# SOCPowerDecoupling.net
KiCad netlist of a schematic drawn in Altium Designer
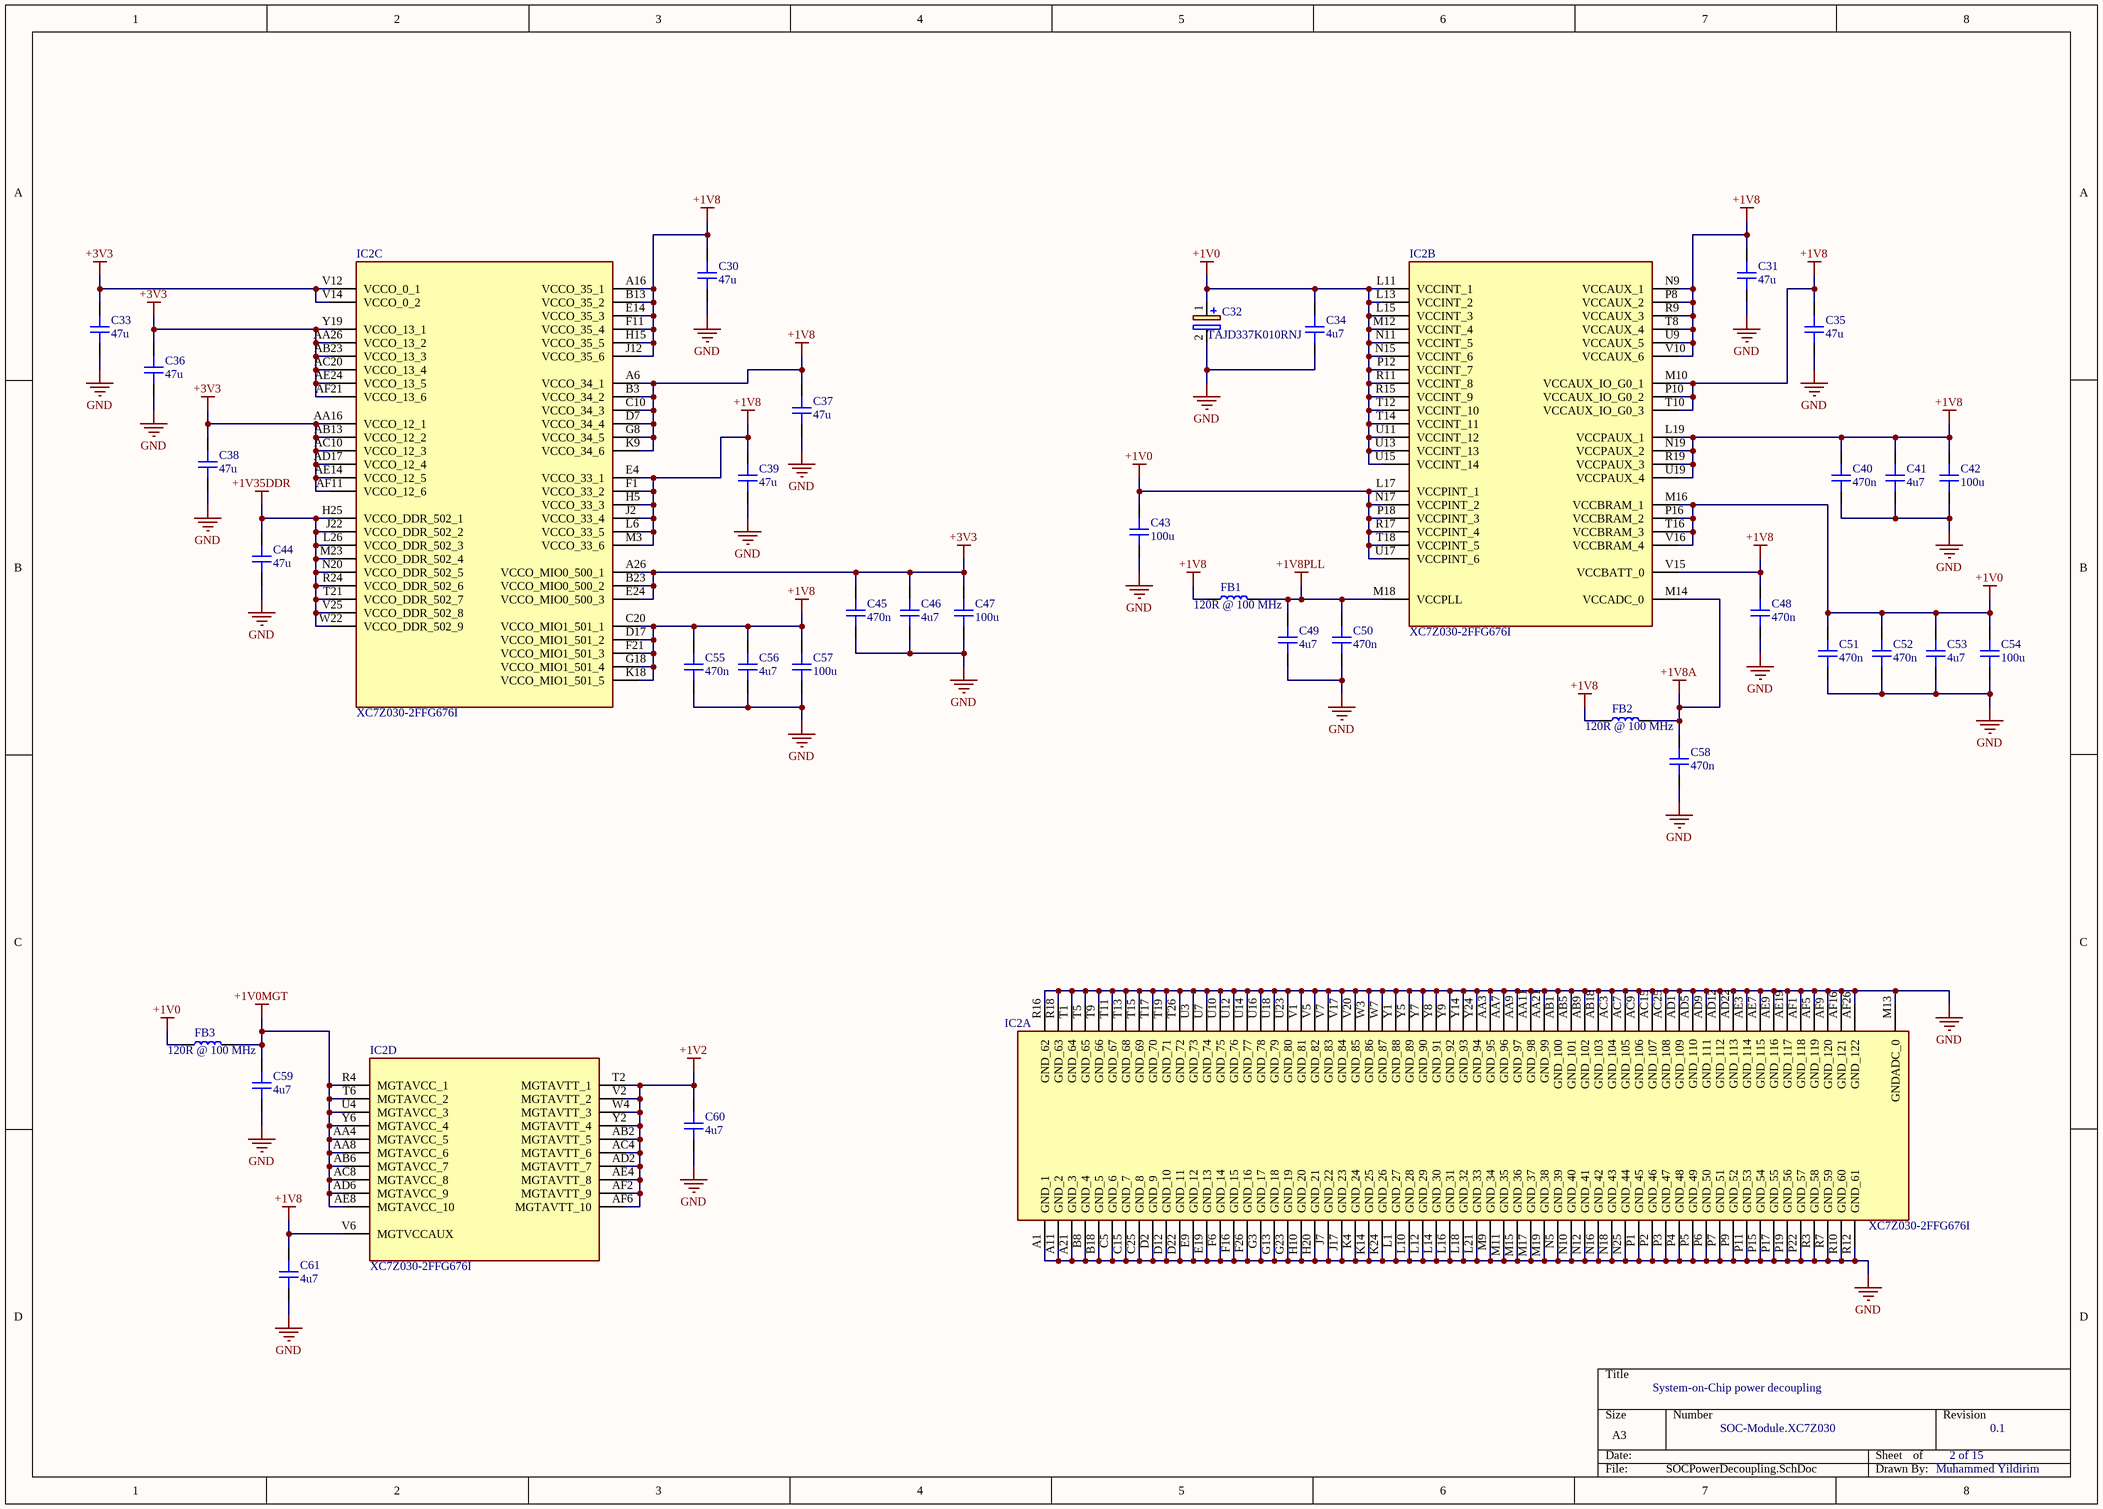
[diagram p0: SOCPowerDecoupling.SchDoc]

(export (version "E")
  (design (tool "Eeschema 10.0.6"))
  (components
    (comp (ref "C30")
      (value "47u")
      (footprint "CAP_0805")
      (description "Capacitor SMD 0805")
      (libsource (lib "Schematic-Lib-PhilsLab") (part "CAP_0805"))
    )
    (comp (ref "C31")
      (value "47u")
      (footprint "CAP_0805")
      (description "Capacitor SMD 0805")
      (libsource (lib "Schematic-Lib-PhilsLab") (part "CAP_0805"))
    )
    (comp (ref "C32")
      (value "TAJD337K010RNJ")
      (footprint "XC7Z030PCBLib:CAPPM7344X310N")
      (description "330 uF Tantalum Capacitor")
      (fields
        (field (name "MANUFACTURER_PART_NUMBER") "T491A106M010AT")
        (field (name "MOUSER PART NUMBER") "80-T491A106M010")
      )
      (libsource (lib "XC7Z030SCHLib") (part "TAJD337K010RNJ"))
    )
    (comp (ref "C33")
      (value "47u")
      (footprint "CAP_0805")
      (description "Capacitor SMD 0805")
      (libsource (lib "Schematic-Lib-PhilsLab") (part "CAP_0805"))
    )
    (comp (ref "C34")
      (value "4u7")
      (footprint "CAP_0402")
      (description "Capacitor SMD 0402")
      (libsource (lib "Schematic-Lib-PhilsLab") (part "CAP_0402"))
    )
    (comp (ref "C35")
      (value "47u")
      (footprint "CAP_0805")
      (description "Capacitor SMD 0805")
      (libsource (lib "Schematic-Lib-PhilsLab") (part "CAP_0805"))
    )
    (comp (ref "C36")
      (value "47u")
      (footprint "CAP_0805")
      (description "Capacitor SMD 0805")
      (libsource (lib "Schematic-Lib-PhilsLab") (part "CAP_0805"))
    )
    (comp (ref "C37")
      (value "47u")
      (footprint "CAP_0805")
      (description "Capacitor SMD 0805")
      (libsource (lib "Schematic-Lib-PhilsLab") (part "CAP_0805"))
    )
    (comp (ref "C38")
      (value "47u")
      (footprint "CAP_0805")
      (description "Capacitor SMD 0805")
      (libsource (lib "Schematic-Lib-PhilsLab") (part "CAP_0805"))
    )
    (comp (ref "C39")
      (value "47u")
      (footprint "CAP_0805")
      (description "Capacitor SMD 0805")
      (libsource (lib "Schematic-Lib-PhilsLab") (part "CAP_0805"))
    )
    (comp (ref "C40")
      (value "470n")
      (footprint "CAP_0201")
      (description "Capacitor SMD 0201")
      (libsource (lib "Schematic-Lib-PhilsLab") (part "CAP_0201"))
    )
    (comp (ref "C41")
      (value "4u7")
      (footprint "CAP_0402")
      (description "Capacitor SMD 0402")
      (libsource (lib "Schematic-Lib-PhilsLab") (part "CAP_0402"))
    )
    (comp (ref "C42")
      (value "100u")
      (footprint "CAP_1210")
      (description "Capacitor SMD 1210")
      (libsource (lib "Schematic-Lib-PhilsLab") (part "CAP_1210"))
    )
    (comp (ref "C43")
      (value "100u")
      (footprint "CAP_1210")
      (description "Capacitor SMD 1210")
      (libsource (lib "Schematic-Lib-PhilsLab") (part "CAP_1210"))
    )
    (comp (ref "C44")
      (value "47u")
      (footprint "CAP_0805")
      (description "Capacitor SMD 0805")
      (libsource (lib "Schematic-Lib-PhilsLab") (part "CAP_0805"))
    )
    (comp (ref "C45")
      (value "470n")
      (footprint "CAP_0201")
      (description "Capacitor SMD 0201")
      (libsource (lib "Schematic-Lib-PhilsLab") (part "CAP_0201"))
    )
    (comp (ref "C46")
      (value "4u7")
      (footprint "CAP_0402")
      (description "Capacitor SMD 0402")
      (libsource (lib "Schematic-Lib-PhilsLab") (part "CAP_0402"))
    )
    (comp (ref "C47")
      (value "100u")
      (footprint "CAP_1210")
      (description "Capacitor SMD 1210")
      (libsource (lib "Schematic-Lib-PhilsLab") (part "CAP_1210"))
    )
    (comp (ref "C48")
      (value "470n")
      (footprint "CAP_0201")
      (description "Capacitor SMD 0201")
      (libsource (lib "Schematic-Lib-PhilsLab") (part "CAP_0201"))
    )
    (comp (ref "C49")
      (value "4u7")
      (footprint "CAP_0402")
      (description "Capacitor SMD 0402")
      (libsource (lib "Schematic-Lib-PhilsLab") (part "CAP_0402"))
    )
    (comp (ref "C50")
      (value "470n")
      (footprint "CAP_0201")
      (description "Capacitor SMD 0201")
      (libsource (lib "Schematic-Lib-PhilsLab") (part "CAP_0201"))
    )
    (comp (ref "C51")
      (value "470n")
      (footprint "CAP_0201")
      (description "Capacitor SMD 0201")
      (libsource (lib "Schematic-Lib-PhilsLab") (part "CAP_0201"))
    )
    (comp (ref "C52")
      (value "470n")
      (footprint "CAP_0201")
      (description "Capacitor SMD 0201")
      (libsource (lib "Schematic-Lib-PhilsLab") (part "CAP_0201"))
    )
    (comp (ref "C53")
      (value "4u7")
      (footprint "CAP_0402")
      (description "Capacitor SMD 0402")
      (libsource (lib "Schematic-Lib-PhilsLab") (part "CAP_0402"))
    )
    (comp (ref "C54")
      (value "100u")
      (footprint "CAP_1210")
      (description "Capacitor SMD 1210")
      (libsource (lib "Schematic-Lib-PhilsLab") (part "CAP_1210"))
    )
    (comp (ref "C55")
      (value "470n")
      (footprint "CAP_0201")
      (description "Capacitor SMD 0201")
      (libsource (lib "Schematic-Lib-PhilsLab") (part "CAP_0201"))
    )
    (comp (ref "C56")
      (value "4u7")
      (footprint "CAP_0402")
      (description "Capacitor SMD 0402")
      (libsource (lib "Schematic-Lib-PhilsLab") (part "CAP_0402"))
    )
    (comp (ref "C57")
      (value "100u")
      (footprint "CAP_1210")
      (description "Capacitor SMD 1210")
      (libsource (lib "Schematic-Lib-PhilsLab") (part "CAP_1210"))
    )
    (comp (ref "C58")
      (value "470n")
      (footprint "CAP_0201")
      (description "Capacitor SMD 0201")
      (libsource (lib "Schematic-Lib-PhilsLab") (part "CAP_0201"))
    )
    (comp (ref "C59")
      (value "4u7")
      (footprint "CAP_0402")
      (description "Capacitor SMD 0402")
      (libsource (lib "Schematic-Lib-PhilsLab") (part "CAP_0402"))
    )
    (comp (ref "C60")
      (value "4u7")
      (footprint "CAP_0402")
      (description "Capacitor SMD 0402")
      (libsource (lib "Schematic-Lib-PhilsLab") (part "CAP_0402"))
    )
    (comp (ref "C61")
      (value "4u7")
      (footprint "CAP_0402")
      (description "Capacitor SMD 0402")
      (libsource (lib "Schematic-Lib-PhilsLab") (part "CAP_0402"))
    )
    (comp (ref "FB1")
      (value "120R @ 100 MHz")
      (footprint "Footprint-Lib-PhilsLab:IND_0201")
      (description "Inductor SMD 0201")
      (fields
        (field (name "MANUFACTURER_PART_NUMBER") "LQP03HQ56NH02D")
        (field (name "MOUSER PART NUMBER") "81-LQP03HQ56NH02D")
      )
      (libsource (lib "Schematic-Lib-PhilsLab") (part "IND_0201"))
    )
    (comp (ref "FB2")
      (value "120R @ 100 MHz")
      (footprint "Footprint-Lib-PhilsLab:IND_0201")
      (description "Inductor SMD 0201")
      (fields
        (field (name "MANUFACTURER_PART_NUMBER") "LQP03HQ56NH02D")
        (field (name "MOUSER PART NUMBER") "81-LQP03HQ56NH02D")
      )
      (libsource (lib "Schematic-Lib-PhilsLab") (part "IND_0201"))
    )
    (comp (ref "FB3")
      (value "120R @ 100 MHz")
      (footprint "Footprint-Lib-PhilsLab:IND_0201")
      (description "Inductor SMD 0201")
      (fields
        (field (name "MANUFACTURER_PART_NUMBER") "LQP03HQ56NH02D")
        (field (name "MOUSER PART NUMBER") "81-LQP03HQ56NH02D")
      )
      (libsource (lib "Schematic-Lib-PhilsLab") (part "IND_0201"))
    )
    (comp (ref "IC2")
      (value "XC7Z030-2FFG676I")
      (footprint "XC7Z030PCBLib:BGA676C100P26X26_2700X2700X324")
      (description "Integrated Circuit")
      (fields (field (name "MOUSER PART NUMBER") "217-XC7Z030-2FFG676I"))
      (libsource (lib "XC7Z030SCHLib") (part "XC7Z030-2FFG676I"))
    )
  )
  (nets
    (net (code "1") (name "+1V0") (class "Default")
      (node (ref "C32") (pin "1") (pinfunction "+_1") (pintype "passive"))
      (node (ref "C34") (pin "2") (pinfunction "2_2") (pintype "passive"))
      (node (ref "C43") (pin "2") (pinfunction "2_2") (pintype "passive"))
      (node (ref "C51") (pin "2") (pinfunction "2_2") (pintype "passive"))
      (node (ref "C52") (pin "2") (pinfunction "2_2") (pintype "passive"))
      (node (ref "C53") (pin "2") (pinfunction "2_2") (pintype "passive"))
      (node (ref "C54") (pin "2") (pinfunction "2_2") (pintype "passive"))
      (node (ref "FB3") (pin "1") (pinfunction "1_1") (pintype "passive"))
      (node (ref "IC2") (pin "L11") (pinfunction "VCCINT_1_L11") (pintype "passive"))
      (node (ref "IC2") (pin "L13") (pinfunction "VCCINT_2_L13") (pintype "passive"))
      (node (ref "IC2") (pin "L15") (pinfunction "VCCINT_3_L15") (pintype "passive"))
      (node (ref "IC2") (pin "L17") (pinfunction "VCCPINT_1_L17") (pintype "passive"))
      (node (ref "IC2") (pin "M12") (pinfunction "VCCINT_4_M12") (pintype "passive"))
      (node (ref "IC2") (pin "M16") (pinfunction "VCCBRAM_1_M16") (pintype "passive"))
      (node (ref "IC2") (pin "N11") (pinfunction "VCCINT_5_N11") (pintype "passive"))
      (node (ref "IC2") (pin "N15") (pinfunction "VCCINT_6_N15") (pintype "passive"))
      (node (ref "IC2") (pin "N17") (pinfunction "VCCPINT_2_N17") (pintype "passive"))
      (node (ref "IC2") (pin "P12") (pinfunction "VCCINT_7_P12") (pintype "passive"))
      (node (ref "IC2") (pin "P16") (pinfunction "VCCBRAM_2_P16") (pintype "passive"))
      (node (ref "IC2") (pin "P18") (pinfunction "VCCPINT_3_P18") (pintype "passive"))
      (node (ref "IC2") (pin "R11") (pinfunction "VCCINT_8_R11") (pintype "passive"))
      (node (ref "IC2") (pin "R15") (pinfunction "VCCINT_9_R15") (pintype "passive"))
      (node (ref "IC2") (pin "R17") (pinfunction "VCCPINT_4_R17") (pintype "passive"))
      (node (ref "IC2") (pin "T12") (pinfunction "VCCINT_10_T12") (pintype "passive"))
      (node (ref "IC2") (pin "T14") (pinfunction "VCCINT_11_T14") (pintype "passive"))
      (node (ref "IC2") (pin "T16") (pinfunction "VCCBRAM_3_T16") (pintype "passive"))
      (node (ref "IC2") (pin "T18") (pinfunction "VCCPINT_5_T18") (pintype "passive"))
      (node (ref "IC2") (pin "U11") (pinfunction "VCCINT_12_U11") (pintype "passive"))
      (node (ref "IC2") (pin "U13") (pinfunction "VCCINT_13_U13") (pintype "passive"))
      (node (ref "IC2") (pin "U15") (pinfunction "VCCINT_14_U15") (pintype "passive"))
      (node (ref "IC2") (pin "U17") (pinfunction "VCCPINT_6_U17") (pintype "passive"))
      (node (ref "IC2") (pin "V16") (pinfunction "VCCBRAM_4_V16") (pintype "passive"))
    )
    (net (code "2") (name "+1V0MGT") (class "Default")
      (node (ref "C59") (pin "2") (pinfunction "2_2") (pintype "passive"))
      (node (ref "FB3") (pin "2") (pinfunction "2_2") (pintype "passive"))
      (node (ref "IC2") (pin "AA4") (pinfunction "MGTAVCC_5_AA4") (pintype "passive"))
      (node (ref "IC2") (pin "AA8") (pinfunction "MGTAVCC_6_AA8") (pintype "passive"))
      (node (ref "IC2") (pin "AB6") (pinfunction "MGTAVCC_7_AB6") (pintype "passive"))
      (node (ref "IC2") (pin "AC8") (pinfunction "MGTAVCC_8_AC8") (pintype "passive"))
      (node (ref "IC2") (pin "AD6") (pinfunction "MGTAVCC_9_AD6") (pintype "passive"))
      (node (ref "IC2") (pin "AE8") (pinfunction "MGTAVCC_10_AE8") (pintype "passive"))
      (node (ref "IC2") (pin "R4") (pinfunction "MGTAVCC_1_R4") (pintype "passive"))
      (node (ref "IC2") (pin "T6") (pinfunction "MGTAVCC_2_T6") (pintype "passive"))
      (node (ref "IC2") (pin "U4") (pinfunction "MGTAVCC_3_U4") (pintype "passive"))
      (node (ref "IC2") (pin "Y6") (pinfunction "MGTAVCC_4_Y6") (pintype "passive"))
    )
    (net (code "3") (name "+1V2") (class "Default")
      (node (ref "C60") (pin "2") (pinfunction "2_2") (pintype "passive"))
      (node (ref "IC2") (pin "AB2") (pinfunction "MGTAVTT_5_AB2") (pintype "passive"))
      (node (ref "IC2") (pin "AC4") (pinfunction "MGTAVTT_6_AC4") (pintype "passive"))
      (node (ref "IC2") (pin "AD2") (pinfunction "MGTAVTT_7_AD2") (pintype "passive"))
      (node (ref "IC2") (pin "AE4") (pinfunction "MGTAVTT_8_AE4") (pintype "passive"))
      (node (ref "IC2") (pin "AF2") (pinfunction "MGTAVTT_9_AF2") (pintype "passive"))
      (node (ref "IC2") (pin "AF6") (pinfunction "MGTAVTT_10_AF6") (pintype "passive"))
      (node (ref "IC2") (pin "T2") (pinfunction "MGTAVTT_1_T2") (pintype "passive"))
      (node (ref "IC2") (pin "V2") (pinfunction "MGTAVTT_2_V2") (pintype "passive"))
      (node (ref "IC2") (pin "W4") (pinfunction "MGTAVTT_3_W4") (pintype "passive"))
      (node (ref "IC2") (pin "Y2") (pinfunction "MGTAVTT_4_Y2") (pintype "passive"))
    )
    (net (code "4") (name "+1V8") (class "Default")
      (node (ref "C30") (pin "2") (pinfunction "2_2") (pintype "passive"))
      (node (ref "C31") (pin "2") (pinfunction "2_2") (pintype "passive"))
      (node (ref "C35") (pin "2") (pinfunction "2_2") (pintype "passive"))
      (node (ref "C37") (pin "2") (pinfunction "2_2") (pintype "passive"))
      (node (ref "C39") (pin "2") (pinfunction "2_2") (pintype "passive"))
      (node (ref "C40") (pin "2") (pinfunction "2_2") (pintype "passive"))
      (node (ref "C41") (pin "2") (pinfunction "2_2") (pintype "passive"))
      (node (ref "C42") (pin "2") (pinfunction "2_2") (pintype "passive"))
      (node (ref "C48") (pin "2") (pinfunction "2_2") (pintype "passive"))
      (node (ref "C55") (pin "2") (pinfunction "2_2") (pintype "passive"))
      (node (ref "C56") (pin "2") (pinfunction "2_2") (pintype "passive"))
      (node (ref "C57") (pin "2") (pinfunction "2_2") (pintype "passive"))
      (node (ref "C61") (pin "2") (pinfunction "2_2") (pintype "passive"))
      (node (ref "FB1") (pin "1") (pinfunction "1_1") (pintype "passive"))
      (node (ref "FB2") (pin "1") (pinfunction "1_1") (pintype "passive"))
      (node (ref "IC2") (pin "A16") (pinfunction "VCCO_35_1_A16") (pintype "passive"))
      (node (ref "IC2") (pin "A6") (pinfunction "VCCO_34_1_A6") (pintype "passive"))
      (node (ref "IC2") (pin "B13") (pinfunction "VCCO_35_2_B13") (pintype "passive"))
      (node (ref "IC2") (pin "B3") (pinfunction "VCCO_34_2_B3") (pintype "passive"))
      (node (ref "IC2") (pin "C10") (pinfunction "VCCO_34_3_C10") (pintype "passive"))
      (node (ref "IC2") (pin "C20") (pinfunction "VCCO_MIO1_501_1_C20") (pintype "passive"))
      (node (ref "IC2") (pin "D17") (pinfunction "VCCO_MIO1_501_2_D17") (pintype "passive"))
      (node (ref "IC2") (pin "D7") (pinfunction "VCCO_34_4_D7") (pintype "passive"))
      (node (ref "IC2") (pin "E14") (pinfunction "VCCO_35_3_E14") (pintype "passive"))
      (node (ref "IC2") (pin "E4") (pinfunction "VCCO_33_1_E4") (pintype "passive"))
      (node (ref "IC2") (pin "F1") (pinfunction "VCCO_33_2_F1") (pintype "passive"))
      (node (ref "IC2") (pin "F11") (pinfunction "VCCO_35_4_F11") (pintype "passive"))
      (node (ref "IC2") (pin "F21") (pinfunction "VCCO_MIO1_501_3_F21") (pintype "passive"))
      (node (ref "IC2") (pin "G18") (pinfunction "VCCO_MIO1_501_4_G18") (pintype "passive"))
      (node (ref "IC2") (pin "G8") (pinfunction "VCCO_34_5_G8") (pintype "passive"))
      (node (ref "IC2") (pin "H15") (pinfunction "VCCO_35_5_H15") (pintype "passive"))
      (node (ref "IC2") (pin "H5") (pinfunction "VCCO_33_3_H5") (pintype "passive"))
      (node (ref "IC2") (pin "J12") (pinfunction "VCCO_35_6_J12") (pintype "passive"))
      (node (ref "IC2") (pin "J2") (pinfunction "VCCO_33_4_J2") (pintype "passive"))
      (node (ref "IC2") (pin "K18") (pinfunction "VCCO_MIO1_501_5_K18") (pintype "passive"))
      (node (ref "IC2") (pin "K9") (pinfunction "VCCO_34_6_K9") (pintype "passive"))
      (node (ref "IC2") (pin "L19") (pinfunction "VCCPAUX_1_L19") (pintype "passive"))
      (node (ref "IC2") (pin "L6") (pinfunction "VCCO_33_5_L6") (pintype "passive"))
      (node (ref "IC2") (pin "M10") (pinfunction "VCCAUX_IO_G0_1_M10") (pintype "passive"))
      (node (ref "IC2") (pin "M3") (pinfunction "VCCO_33_6_M3") (pintype "passive"))
      (node (ref "IC2") (pin "N19") (pinfunction "VCCPAUX_2_N19") (pintype "passive"))
      (node (ref "IC2") (pin "N9") (pinfunction "VCCAUX_1_N9") (pintype "passive"))
      (node (ref "IC2") (pin "P10") (pinfunction "VCCAUX_IO_G0_2_P10") (pintype "passive"))
      (node (ref "IC2") (pin "P8") (pinfunction "VCCAUX_2_P8") (pintype "passive"))
      (node (ref "IC2") (pin "R19") (pinfunction "VCCPAUX_3_R19") (pintype "passive"))
      (node (ref "IC2") (pin "R9") (pinfunction "VCCAUX_3_R9") (pintype "passive"))
      (node (ref "IC2") (pin "T10") (pinfunction "VCCAUX_IO_G0_3_T10") (pintype "passive"))
      (node (ref "IC2") (pin "T8") (pinfunction "VCCAUX_4_T8") (pintype "passive"))
      (node (ref "IC2") (pin "U19") (pinfunction "VCCPAUX_4_U19") (pintype "passive"))
      (node (ref "IC2") (pin "U9") (pinfunction "VCCAUX_5_U9") (pintype "passive"))
      (node (ref "IC2") (pin "V10") (pinfunction "VCCAUX_6_V10") (pintype "passive"))
      (node (ref "IC2") (pin "V15") (pinfunction "VCCBATT_0_V15") (pintype "passive"))
      (node (ref "IC2") (pin "V6") (pinfunction "MGTVCCAUX_V6") (pintype "passive"))
    )
    (net (code "5") (name "+1V8A") (class "Default")
      (node (ref "C58") (pin "2") (pinfunction "2_2") (pintype "passive"))
      (node (ref "FB2") (pin "2") (pinfunction "2_2") (pintype "passive"))
      (node (ref "IC2") (pin "M14") (pinfunction "VCCADC_0_M14") (pintype "passive"))
    )
    (net (code "6") (name "+1V8PLL") (class "Default")
      (node (ref "C49") (pin "2") (pinfunction "2_2") (pintype "passive"))
      (node (ref "C50") (pin "2") (pinfunction "2_2") (pintype "passive"))
      (node (ref "FB1") (pin "2") (pinfunction "2_2") (pintype "passive"))
      (node (ref "IC2") (pin "M18") (pinfunction "VCCPLL_M18") (pintype "passive"))
    )
    (net (code "7") (name "+1V35DDR") (class "Default")
      (node (ref "C44") (pin "2") (pinfunction "2_2") (pintype "passive"))
      (node (ref "IC2") (pin "H25") (pinfunction "VCCO_DDR_502_1_H25") (pintype "passive"))
      (node (ref "IC2") (pin "J22") (pinfunction "VCCO_DDR_502_2_J22") (pintype "passive"))
      (node (ref "IC2") (pin "L26") (pinfunction "VCCO_DDR_502_3_L26") (pintype "passive"))
      (node (ref "IC2") (pin "M23") (pinfunction "VCCO_DDR_502_4_M23") (pintype "passive"))
      (node (ref "IC2") (pin "N20") (pinfunction "VCCO_DDR_502_5_N20") (pintype "passive"))
      (node (ref "IC2") (pin "R24") (pinfunction "VCCO_DDR_502_6_R24") (pintype "passive"))
      (node (ref "IC2") (pin "T21") (pinfunction "VCCO_DDR_502_7_T21") (pintype "passive"))
      (node (ref "IC2") (pin "V25") (pinfunction "VCCO_DDR_502_8_V25") (pintype "passive"))
      (node (ref "IC2") (pin "W22") (pinfunction "VCCO_DDR_502_9_W22") (pintype "passive"))
    )
    (net (code "8") (name "+3V3") (class "Default")
      (node (ref "C33") (pin "2") (pinfunction "2_2") (pintype "passive"))
      (node (ref "C36") (pin "2") (pinfunction "2_2") (pintype "passive"))
      (node (ref "C38") (pin "2") (pinfunction "2_2") (pintype "passive"))
      (node (ref "C45") (pin "2") (pinfunction "2_2") (pintype "passive"))
      (node (ref "C46") (pin "2") (pinfunction "2_2") (pintype "passive"))
      (node (ref "C47") (pin "2") (pinfunction "2_2") (pintype "passive"))
      (node (ref "IC2") (pin "A26") (pinfunction "VCCO_MIO0_500_1_A26") (pintype "passive"))
      (node (ref "IC2") (pin "AA16") (pinfunction "VCCO_12_1_AA16") (pintype "passive"))
      (node (ref "IC2") (pin "AA26") (pinfunction "VCCO_13_2_AA26") (pintype "passive"))
      (node (ref "IC2") (pin "AB13") (pinfunction "VCCO_12_2_AB13") (pintype "passive"))
      (node (ref "IC2") (pin "AB23") (pinfunction "VCCO_13_3_AB23") (pintype "passive"))
      (node (ref "IC2") (pin "AC10") (pinfunction "VCCO_12_3_AC10") (pintype "passive"))
      (node (ref "IC2") (pin "AC20") (pinfunction "VCCO_13_4_AC20") (pintype "passive"))
      (node (ref "IC2") (pin "AD17") (pinfunction "VCCO_12_4_AD17") (pintype "passive"))
      (node (ref "IC2") (pin "AE14") (pinfunction "VCCO_12_5_AE14") (pintype "passive"))
      (node (ref "IC2") (pin "AE24") (pinfunction "VCCO_13_5_AE24") (pintype "passive"))
      (node (ref "IC2") (pin "AF11") (pinfunction "VCCO_12_6_AF11") (pintype "passive"))
      (node (ref "IC2") (pin "AF21") (pinfunction "VCCO_13_6_AF21") (pintype "passive"))
      (node (ref "IC2") (pin "B23") (pinfunction "VCCO_MIO0_500_2_B23") (pintype "passive"))
      (node (ref "IC2") (pin "E24") (pinfunction "VCCO_MIO0_500_3_E24") (pintype "passive"))
      (node (ref "IC2") (pin "V12") (pinfunction "VCCO_0_1_V12") (pintype "passive"))
      (node (ref "IC2") (pin "V14") (pinfunction "VCCO_0_2_V14") (pintype "passive"))
      (node (ref "IC2") (pin "Y19") (pinfunction "VCCO_13_1_Y19") (pintype "passive"))
    )
    (net (code "9") (name "GND") (class "Default")
      (node (ref "C30") (pin "1") (pinfunction "1_1") (pintype "passive"))
      (node (ref "C31") (pin "1") (pinfunction "1_1") (pintype "passive"))
      (node (ref "C32") (pin "2") (pinfunction "-_2") (pintype "passive"))
      (node (ref "C33") (pin "1") (pinfunction "1_1") (pintype "passive"))
      (node (ref "C34") (pin "1") (pinfunction "1_1") (pintype "passive"))
      (node (ref "C35") (pin "1") (pinfunction "1_1") (pintype "passive"))
      (node (ref "C36") (pin "1") (pinfunction "1_1") (pintype "passive"))
      (node (ref "C37") (pin "1") (pinfunction "1_1") (pintype "passive"))
      (node (ref "C38") (pin "1") (pinfunction "1_1") (pintype "passive"))
      (node (ref "C39") (pin "1") (pinfunction "1_1") (pintype "passive"))
      (node (ref "C40") (pin "1") (pinfunction "1_1") (pintype "passive"))
      (node (ref "C41") (pin "1") (pinfunction "1_1") (pintype "passive"))
      (node (ref "C42") (pin "1") (pinfunction "1_1") (pintype "passive"))
      (node (ref "C43") (pin "1") (pinfunction "1_1") (pintype "passive"))
      (node (ref "C44") (pin "1") (pinfunction "1_1") (pintype "passive"))
      (node (ref "C45") (pin "1") (pinfunction "1_1") (pintype "passive"))
      (node (ref "C46") (pin "1") (pinfunction "1_1") (pintype "passive"))
      (node (ref "C47") (pin "1") (pinfunction "1_1") (pintype "passive"))
      (node (ref "C48") (pin "1") (pinfunction "1_1") (pintype "passive"))
      (node (ref "C49") (pin "1") (pinfunction "1_1") (pintype "passive"))
      (node (ref "C50") (pin "1") (pinfunction "1_1") (pintype "passive"))
      (node (ref "C51") (pin "1") (pinfunction "1_1") (pintype "passive"))
      (node (ref "C52") (pin "1") (pinfunction "1_1") (pintype "passive"))
      (node (ref "C53") (pin "1") (pinfunction "1_1") (pintype "passive"))
      (node (ref "C54") (pin "1") (pinfunction "1_1") (pintype "passive"))
      (node (ref "C55") (pin "1") (pinfunction "1_1") (pintype "passive"))
      (node (ref "C56") (pin "1") (pinfunction "1_1") (pintype "passive"))
      (node (ref "C57") (pin "1") (pinfunction "1_1") (pintype "passive"))
      (node (ref "C58") (pin "1") (pinfunction "1_1") (pintype "passive"))
      (node (ref "C59") (pin "1") (pinfunction "1_1") (pintype "passive"))
      (node (ref "C60") (pin "1") (pinfunction "1_1") (pintype "passive"))
      (node (ref "C61") (pin "1") (pinfunction "1_1") (pintype "passive"))
      (node (ref "IC2") (pin "A1") (pinfunction "GND_1_A1") (pintype "passive"))
      (node (ref "IC2") (pin "A11") (pinfunction "GND_2_A11") (pintype "passive"))
      (node (ref "IC2") (pin "A21") (pinfunction "GND_3_A21") (pintype "passive"))
      (node (ref "IC2") (pin "AA11") (pinfunction "GND_98_AA11") (pintype "passive"))
      (node (ref "IC2") (pin "AA21") (pinfunction "GND_99_AA21") (pintype "passive"))
      (node (ref "IC2") (pin "AA3") (pinfunction "GND_95_AA3") (pintype "passive"))
      (node (ref "IC2") (pin "AA7") (pinfunction "GND_96_AA7") (pintype "passive"))
      (node (ref "IC2") (pin "AA9") (pinfunction "GND_97_AA9") (pintype "passive"))
      (node (ref "IC2") (pin "AB1") (pinfunction "GND_100_AB1") (pintype "passive"))
      (node (ref "IC2") (pin "AB18") (pinfunction "GND_103_AB18") (pintype "passive"))
      (node (ref "IC2") (pin "AB5") (pinfunction "GND_101_AB5") (pintype "passive"))
      (node (ref "IC2") (pin "AB9") (pinfunction "GND_102_AB9") (pintype "passive"))
      (node (ref "IC2") (pin "AC15") (pinfunction "GND_107_AC15") (pintype "passive"))
      (node (ref "IC2") (pin "AC25") (pinfunction "GND_108_AC25") (pintype "passive"))
      (node (ref "IC2") (pin "AC3") (pinfunction "GND_104_AC3") (pintype "passive"))
      (node (ref "IC2") (pin "AC7") (pinfunction "GND_105_AC7") (pintype "passive"))
      (node (ref "IC2") (pin "AC9") (pinfunction "GND_106_AC9") (pintype "passive"))
      (node (ref "IC2") (pin "AD1") (pinfunction "GND_109_AD1") (pintype "passive"))
      (node (ref "IC2") (pin "AD12") (pinfunction "GND_112_AD12") (pintype "passive"))
      (node (ref "IC2") (pin "AD22") (pinfunction "GND_113_AD22") (pintype "passive"))
      (node (ref "IC2") (pin "AD5") (pinfunction "GND_110_AD5") (pintype "passive"))
      (node (ref "IC2") (pin "AD9") (pinfunction "GND_111_AD9") (pintype "passive"))
      (node (ref "IC2") (pin "AE19") (pinfunction "GND_117_AE19") (pintype "passive"))
      (node (ref "IC2") (pin "AE3") (pinfunction "GND_114_AE3") (pintype "passive"))
      (node (ref "IC2") (pin "AE7") (pinfunction "GND_115_AE7") (pintype "passive"))
      (node (ref "IC2") (pin "AE9") (pinfunction "GND_116_AE9") (pintype "passive"))
      (node (ref "IC2") (pin "AF1") (pinfunction "GND_118_AF1") (pintype "passive"))
      (node (ref "IC2") (pin "AF16") (pinfunction "GND_121_AF16") (pintype "passive"))
      (node (ref "IC2") (pin "AF26") (pinfunction "GND_122_AF26") (pintype "passive"))
      (node (ref "IC2") (pin "AF5") (pinfunction "GND_119_AF5") (pintype "passive"))
      (node (ref "IC2") (pin "AF9") (pinfunction "GND_120_AF9") (pintype "passive"))
      (node (ref "IC2") (pin "B18") (pinfunction "GND_5_B18") (pintype "passive"))
      (node (ref "IC2") (pin "B8") (pinfunction "GND_4_B8") (pintype "passive"))
      (node (ref "IC2") (pin "C15") (pinfunction "GND_7_C15") (pintype "passive"))
      (node (ref "IC2") (pin "C25") (pinfunction "GND_8_C25") (pintype "passive"))
      (node (ref "IC2") (pin "C5") (pinfunction "GND_6_C5") (pintype "passive"))
      (node (ref "IC2") (pin "D12") (pinfunction "GND_10_D12") (pintype "passive"))
      (node (ref "IC2") (pin "D2") (pinfunction "GND_9_D2") (pintype "passive"))
      (node (ref "IC2") (pin "D22") (pinfunction "GND_11_D22") (pintype "passive"))
      (node (ref "IC2") (pin "E19") (pinfunction "GND_13_E19") (pintype "passive"))
      (node (ref "IC2") (pin "E9") (pinfunction "GND_12_E9") (pintype "passive"))
      (node (ref "IC2") (pin "F16") (pinfunction "GND_15_F16") (pintype "passive"))
      (node (ref "IC2") (pin "F26") (pinfunction "GND_16_F26") (pintype "passive"))
      (node (ref "IC2") (pin "F6") (pinfunction "GND_14_F6") (pintype "passive"))
      (node (ref "IC2") (pin "G13") (pinfunction "GND_18_G13") (pintype "passive"))
      (node (ref "IC2") (pin "G23") (pinfunction "GND_19_G23") (pintype "passive"))
      (node (ref "IC2") (pin "G3") (pinfunction "GND_17_G3") (pintype "passive"))
      (node (ref "IC2") (pin "H10") (pinfunction "GND_20_H10") (pintype "passive"))
      (node (ref "IC2") (pin "H20") (pinfunction "GND_21_H20") (pintype "passive"))
      (node (ref "IC2") (pin "J17") (pinfunction "GND_23_J17") (pintype "passive"))
      (node (ref "IC2") (pin "J7") (pinfunction "GND_22_J7") (pintype "passive"))
      (node (ref "IC2") (pin "K14") (pinfunction "GND_25_K14") (pintype "passive"))
      (node (ref "IC2") (pin "K24") (pinfunction "GND_26_K24") (pintype "passive"))
      (node (ref "IC2") (pin "K4") (pinfunction "GND_24_K4") (pintype "passive"))
      (node (ref "IC2") (pin "L1") (pinfunction "GND_27_L1") (pintype "passive"))
      (node (ref "IC2") (pin "L10") (pinfunction "GND_28_L10") (pintype "passive"))
      (node (ref "IC2") (pin "L12") (pinfunction "GND_29_L12") (pintype "passive"))
      (node (ref "IC2") (pin "L14") (pinfunction "GND_30_L14") (pintype "passive"))
      (node (ref "IC2") (pin "L16") (pinfunction "GND_31_L16") (pintype "passive"))
      (node (ref "IC2") (pin "L18") (pinfunction "GND_32_L18") (pintype "passive"))
      (node (ref "IC2") (pin "L21") (pinfunction "GND_33_L21") (pintype "passive"))
      (node (ref "IC2") (pin "M11") (pinfunction "GND_35_M11") (pintype "passive"))
      (node (ref "IC2") (pin "M13") (pinfunction "GNDADC_0_M13") (pintype "passive"))
      (node (ref "IC2") (pin "M15") (pinfunction "GND_36_M15") (pintype "passive"))
      (node (ref "IC2") (pin "M17") (pinfunction "GND_37_M17") (pintype "passive"))
      (node (ref "IC2") (pin "M19") (pinfunction "GND_38_M19") (pintype "passive"))
      (node (ref "IC2") (pin "M9") (pinfunction "GND_34_M9") (pintype "passive"))
      (node (ref "IC2") (pin "N10") (pinfunction "GND_40_N10") (pintype "passive"))
      (node (ref "IC2") (pin "N12") (pinfunction "GND_41_N12") (pintype "passive"))
      (node (ref "IC2") (pin "N16") (pinfunction "GND_42_N16") (pintype "passive"))
      (node (ref "IC2") (pin "N18") (pinfunction "GND_43_N18") (pintype "passive"))
      (node (ref "IC2") (pin "N25") (pinfunction "GND_44_N25") (pintype "passive"))
      (node (ref "IC2") (pin "N5") (pinfunction "GND_39_N5") (pintype "passive"))
      (node (ref "IC2") (pin "P1") (pinfunction "GND_45_P1") (pintype "passive"))
      (node (ref "IC2") (pin "P11") (pinfunction "GND_53_P11") (pintype "passive"))
      (node (ref "IC2") (pin "P15") (pinfunction "GND_54_P15") (pintype "passive"))
      (node (ref "IC2") (pin "P17") (pinfunction "GND_55_P17") (pintype "passive"))
      (node (ref "IC2") (pin "P19") (pinfunction "GND_56_P19") (pintype "passive"))
      (node (ref "IC2") (pin "P2") (pinfunction "GND_46_P2") (pintype "passive"))
      (node (ref "IC2") (pin "P22") (pinfunction "GND_57_P22") (pintype "passive"))
      (node (ref "IC2") (pin "P3") (pinfunction "GND_47_P3") (pintype "passive"))
      (node (ref "IC2") (pin "P4") (pinfunction "GND_48_P4") (pintype "passive"))
      (node (ref "IC2") (pin "P5") (pinfunction "GND_49_P5") (pintype "passive"))
      (node (ref "IC2") (pin "P6") (pinfunction "GND_50_P6") (pintype "passive"))
      (node (ref "IC2") (pin "P7") (pinfunction "GND_51_P7") (pintype "passive"))
      (node (ref "IC2") (pin "P9") (pinfunction "GND_52_P9") (pintype "passive"))
      (node (ref "IC2") (pin "R10") (pinfunction "GND_60_R10") (pintype "passive"))
      (node (ref "IC2") (pin "R12") (pinfunction "GND_61_R12") (pintype "passive"))
      (node (ref "IC2") (pin "R16") (pinfunction "GND_62_R16") (pintype "passive"))
      (node (ref "IC2") (pin "R18") (pinfunction "GND_63_R18") (pintype "passive"))
      (node (ref "IC2") (pin "R3") (pinfunction "GND_58_R3") (pintype "passive"))
      (node (ref "IC2") (pin "R7") (pinfunction "GND_59_R7") (pintype "passive"))
      (node (ref "IC2") (pin "T1") (pinfunction "GND_64_T1") (pintype "passive"))
      (node (ref "IC2") (pin "T11") (pinfunction "GND_67_T11") (pintype "passive"))
      (node (ref "IC2") (pin "T13") (pinfunction "GND_68_T13") (pintype "passive"))
      (node (ref "IC2") (pin "T15") (pinfunction "GND_69_T15") (pintype "passive"))
      (node (ref "IC2") (pin "T17") (pinfunction "GND_70_T17") (pintype "passive"))
      (node (ref "IC2") (pin "T19") (pinfunction "GND_71_T19") (pintype "passive"))
      (node (ref "IC2") (pin "T26") (pinfunction "GND_72_T26") (pintype "passive"))
      (node (ref "IC2") (pin "T5") (pinfunction "GND_65_T5") (pintype "passive"))
      (node (ref "IC2") (pin "T9") (pinfunction "GND_66_T9") (pintype "passive"))
      (node (ref "IC2") (pin "U10") (pinfunction "GND_75_U10") (pintype "passive"))
      (node (ref "IC2") (pin "U12") (pinfunction "GND_76_U12") (pintype "passive"))
      (node (ref "IC2") (pin "U14") (pinfunction "GND_77_U14") (pintype "passive"))
      (node (ref "IC2") (pin "U16") (pinfunction "GND_78_U16") (pintype "passive"))
      (node (ref "IC2") (pin "U18") (pinfunction "GND_79_U18") (pintype "passive"))
      (node (ref "IC2") (pin "U23") (pinfunction "GND_80_U23") (pintype "passive"))
      (node (ref "IC2") (pin "U3") (pinfunction "GND_73_U3") (pintype "passive"))
      (node (ref "IC2") (pin "U7") (pinfunction "GND_74_U7") (pintype "passive"))
      (node (ref "IC2") (pin "V1") (pinfunction "GND_81_V1") (pintype "passive"))
      (node (ref "IC2") (pin "V17") (pinfunction "GND_84_V17") (pintype "passive"))
      (node (ref "IC2") (pin "V20") (pinfunction "GND_85_V20") (pintype "passive"))
      (node (ref "IC2") (pin "V5") (pinfunction "GND_82_V5") (pintype "passive"))
      (node (ref "IC2") (pin "V7") (pinfunction "GND_83_V7") (pintype "passive"))
      (node (ref "IC2") (pin "W3") (pinfunction "GND_86_W3") (pintype "passive"))
      (node (ref "IC2") (pin "W7") (pinfunction "GND_87_W7") (pintype "passive"))
      (node (ref "IC2") (pin "Y1") (pinfunction "GND_88_Y1") (pintype "passive"))
      (node (ref "IC2") (pin "Y14") (pinfunction "GND_93_Y14") (pintype "passive"))
      (node (ref "IC2") (pin "Y24") (pinfunction "GND_94_Y24") (pintype "passive"))
      (node (ref "IC2") (pin "Y5") (pinfunction "GND_89_Y5") (pintype "passive"))
      (node (ref "IC2") (pin "Y7") (pinfunction "GND_90_Y7") (pintype "passive"))
      (node (ref "IC2") (pin "Y8") (pinfunction "GND_91_Y8") (pintype "passive"))
      (node (ref "IC2") (pin "Y9") (pinfunction "GND_92_Y9") (pintype "passive"))
    )
  )
)
